# PoE.net
KiCad netlist of a schematic drawn in EAGLE
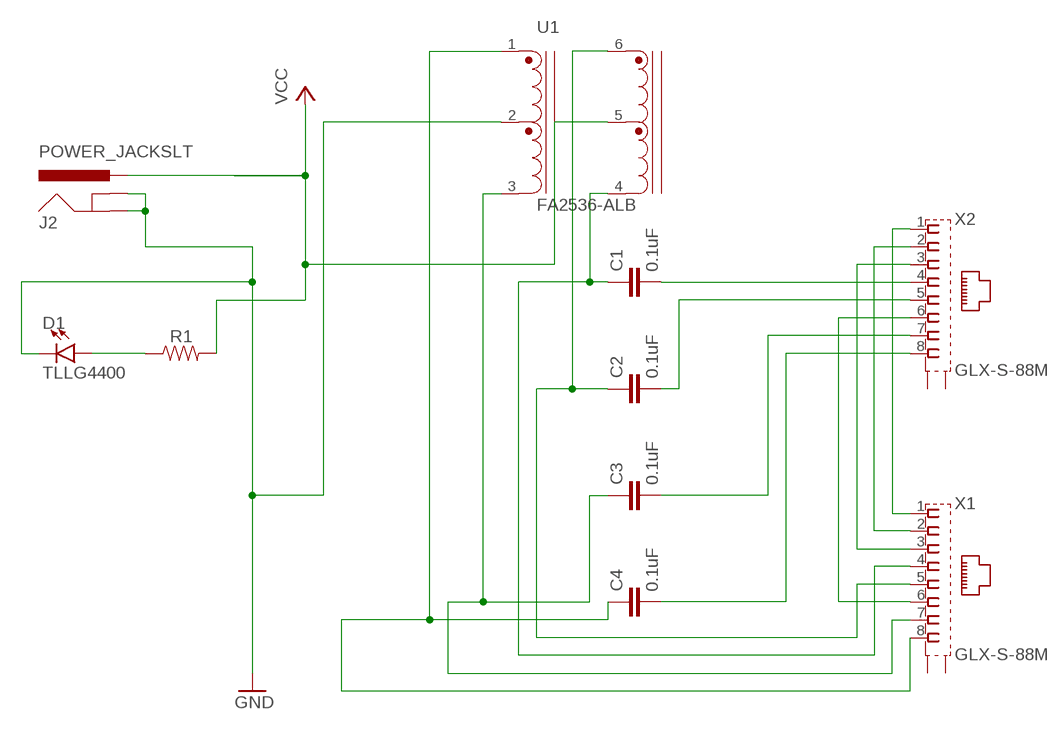
[diagram p0: schematic, sheet 1]

(export (version "E")
  (design (tool "Eeschema 10.0.6"))
  (components
    (comp (ref "C1")
      (value "0.1uF")
      (footprint "eagle-import:CAP-PTH-SMALL-KIT")
      (libsource (lib "eagle-import") (part "0.1UF-KIT-EZ-50V-20%"))
    )
    (comp (ref "C2")
      (value "0.1uF")
      (footprint "eagle-import:CAP-PTH-SMALL-KIT")
      (libsource (lib "eagle-import") (part "0.1UF-KIT-EZ-50V-20%"))
    )
    (comp (ref "C3")
      (value "0.1uF")
      (footprint "eagle-import:CAP-PTH-SMALL-KIT")
      (libsource (lib "eagle-import") (part "0.1UF-KIT-EZ-50V-20%"))
    )
    (comp (ref "C4")
      (value "0.1uF")
      (footprint "eagle-import:CAP-PTH-SMALL-KIT")
      (libsource (lib "eagle-import") (part "0.1UF-KIT-EZ-50V-20%"))
    )
    (comp (ref "D1")
      (value "TLLG4400")
      (footprint "eagle-import:LED_3MM")
      (libsource (lib "eagle-import") (part "LED3MM"))
    )
    (comp (ref "J2")
      (value "POWER_JACKSLT")
      (footprint "eagle-import:POWER_JACK_SLOT")
      (libsource (lib "eagle-import") (part "POWER_JACKSLT"))
    )
    (comp (ref "R1")
      (value "RESISTORAXIAL-0.3")
      (footprint "eagle-import:AXIAL-0.3")
      (libsource (lib "eagle-import") (part "RESISTORAXIAL-0.3"))
    )
    (comp (ref "U1")
      (value "FA2536-ALB")
      (footprint "eagle-import:POE_FA2536-ALB")
      (fields (field (name "MF") "Coilcraft"))
      (libsource (lib "eagle-import") (part "FA2536-ALB"))
    )
    (comp (ref "X1")
      (value "GLX-S-88M")
      (footprint "eagle-import:GLX-S-88M")
      (libsource (lib "eagle-import") (part "GLX-S-88M"))
    )
    (comp (ref "X2")
      (value "GLX-S-88M")
      (footprint "eagle-import:GLX-S-88M")
      (libsource (lib "eagle-import") (part "GLX-S-88M"))
    )
  )
  (nets
    (net (code "1") (name "GND") (class "Default")
      (node (ref "D1") (pin "K") (pinfunction "C_K") (pintype "passive"))
      (node (ref "J2") (pin "GND@1") (pinfunction "GNDBREAK_GND@1") (pintype "bidirectional"))
      (node (ref "J2") (pin "GND@2") (pinfunction "GND_GND@2") (pintype "bidirectional"))
      (node (ref "U1") (pin "2") (pinfunction "2_2") (pintype "passive"))
    )
    (net (code "2") (name "Net-(C1-Pad1)") (class "Default")
      (node (ref "C1") (pin "1") (pinfunction "1_1") (pintype "passive"))
      (node (ref "U1") (pin "4") (pinfunction "4_4") (pintype "passive"))
      (node (ref "X1") (pin "4") (pinfunction "4_4") (pintype "passive"))
    )
    (net (code "3") (name "Net-(C1-Pad2)") (class "Default")
      (node (ref "C1") (pin "2") (pinfunction "2_2") (pintype "passive"))
      (node (ref "X2") (pin "4") (pinfunction "4_4") (pintype "passive"))
    )
    (net (code "4") (name "Net-(C2-Pad1)") (class "Default")
      (node (ref "C2") (pin "1") (pinfunction "1_1") (pintype "passive"))
      (node (ref "U1") (pin "6") (pinfunction "6_6") (pintype "passive"))
      (node (ref "X1") (pin "5") (pinfunction "5_5") (pintype "passive"))
    )
    (net (code "5") (name "Net-(C2-Pad2)") (class "Default")
      (node (ref "C2") (pin "2") (pinfunction "2_2") (pintype "passive"))
      (node (ref "X2") (pin "5") (pinfunction "5_5") (pintype "passive"))
    )
    (net (code "6") (name "Net-(C3-Pad1)") (class "Default")
      (node (ref "C3") (pin "1") (pinfunction "1_1") (pintype "passive"))
      (node (ref "U1") (pin "3") (pinfunction "3_3") (pintype "passive"))
      (node (ref "X1") (pin "7") (pinfunction "7_7") (pintype "passive"))
    )
    (net (code "7") (name "Net-(C3-Pad2)") (class "Default")
      (node (ref "C3") (pin "2") (pinfunction "2_2") (pintype "passive"))
      (node (ref "X2") (pin "7") (pinfunction "7_7") (pintype "passive"))
    )
    (net (code "8") (name "Net-(C4-Pad1)") (class "Default")
      (node (ref "C4") (pin "1") (pinfunction "1_1") (pintype "passive"))
      (node (ref "U1") (pin "1") (pinfunction "1_1") (pintype "passive"))
      (node (ref "X1") (pin "8") (pinfunction "8_8") (pintype "passive"))
    )
    (net (code "9") (name "Net-(C4-Pad2)") (class "Default")
      (node (ref "C4") (pin "2") (pinfunction "2_2") (pintype "passive"))
      (node (ref "X2") (pin "8") (pinfunction "8_8") (pintype "passive"))
    )
    (net (code "10") (name "Net-(R1-1)") (class "Default")
      (node (ref "D1") (pin "A") (pinfunction "A_A") (pintype "passive"))
      (node (ref "R1") (pin "P$1") (pinfunction "1_P$1") (pintype "passive"))
    )
    (net (code "11") (name "Net-(X1-Pad1)") (class "Default")
      (node (ref "X1") (pin "1") (pinfunction "1_1") (pintype "passive"))
      (node (ref "X2") (pin "1") (pinfunction "1_1") (pintype "passive"))
    )
    (net (code "12") (name "Net-(X1-Pad2)") (class "Default")
      (node (ref "X1") (pin "2") (pinfunction "2_2") (pintype "passive"))
      (node (ref "X2") (pin "2") (pinfunction "2_2") (pintype "passive"))
    )
    (net (code "13") (name "Net-(X1-Pad3)") (class "Default")
      (node (ref "X1") (pin "3") (pinfunction "3_3") (pintype "passive"))
      (node (ref "X2") (pin "3") (pinfunction "3_3") (pintype "passive"))
    )
    (net (code "14") (name "Net-(X1-Pad6)") (class "Default")
      (node (ref "X1") (pin "6") (pinfunction "6_6") (pintype "passive"))
      (node (ref "X2") (pin "6") (pinfunction "6_6") (pintype "passive"))
    )
    (net (code "15") (name "VCC") (class "Default")
      (node (ref "J2") (pin "PWR") (pinfunction "PWR_PWR") (pintype "bidirectional"))
      (node (ref "R1") (pin "P$2") (pinfunction "2_P$2") (pintype "passive"))
      (node (ref "U1") (pin "5") (pinfunction "5_5") (pintype "passive"))
    )
    (net (code "16") (name "unconnected-(X1-PadS1)") (class "Default")
      (node (ref "X1") (pin "S1") (pinfunction "S1_S1") (pintype "passive"))
    )
    (net (code "17") (name "unconnected-(X1-PadS2)") (class "Default")
      (node (ref "X1") (pin "S2") (pinfunction "S2_S2") (pintype "passive"))
    )
    (net (code "18") (name "unconnected-(X2-PadS1)") (class "Default")
      (node (ref "X2") (pin "S1") (pinfunction "S1_S1") (pintype "passive"))
    )
    (net (code "19") (name "unconnected-(X2-PadS2)") (class "Default")
      (node (ref "X2") (pin "S2") (pinfunction "S2_S2") (pintype "passive"))
    )
  )
)
